# TOP_Sheet.net
KiCad netlist of a schematic drawn in Altium Designer
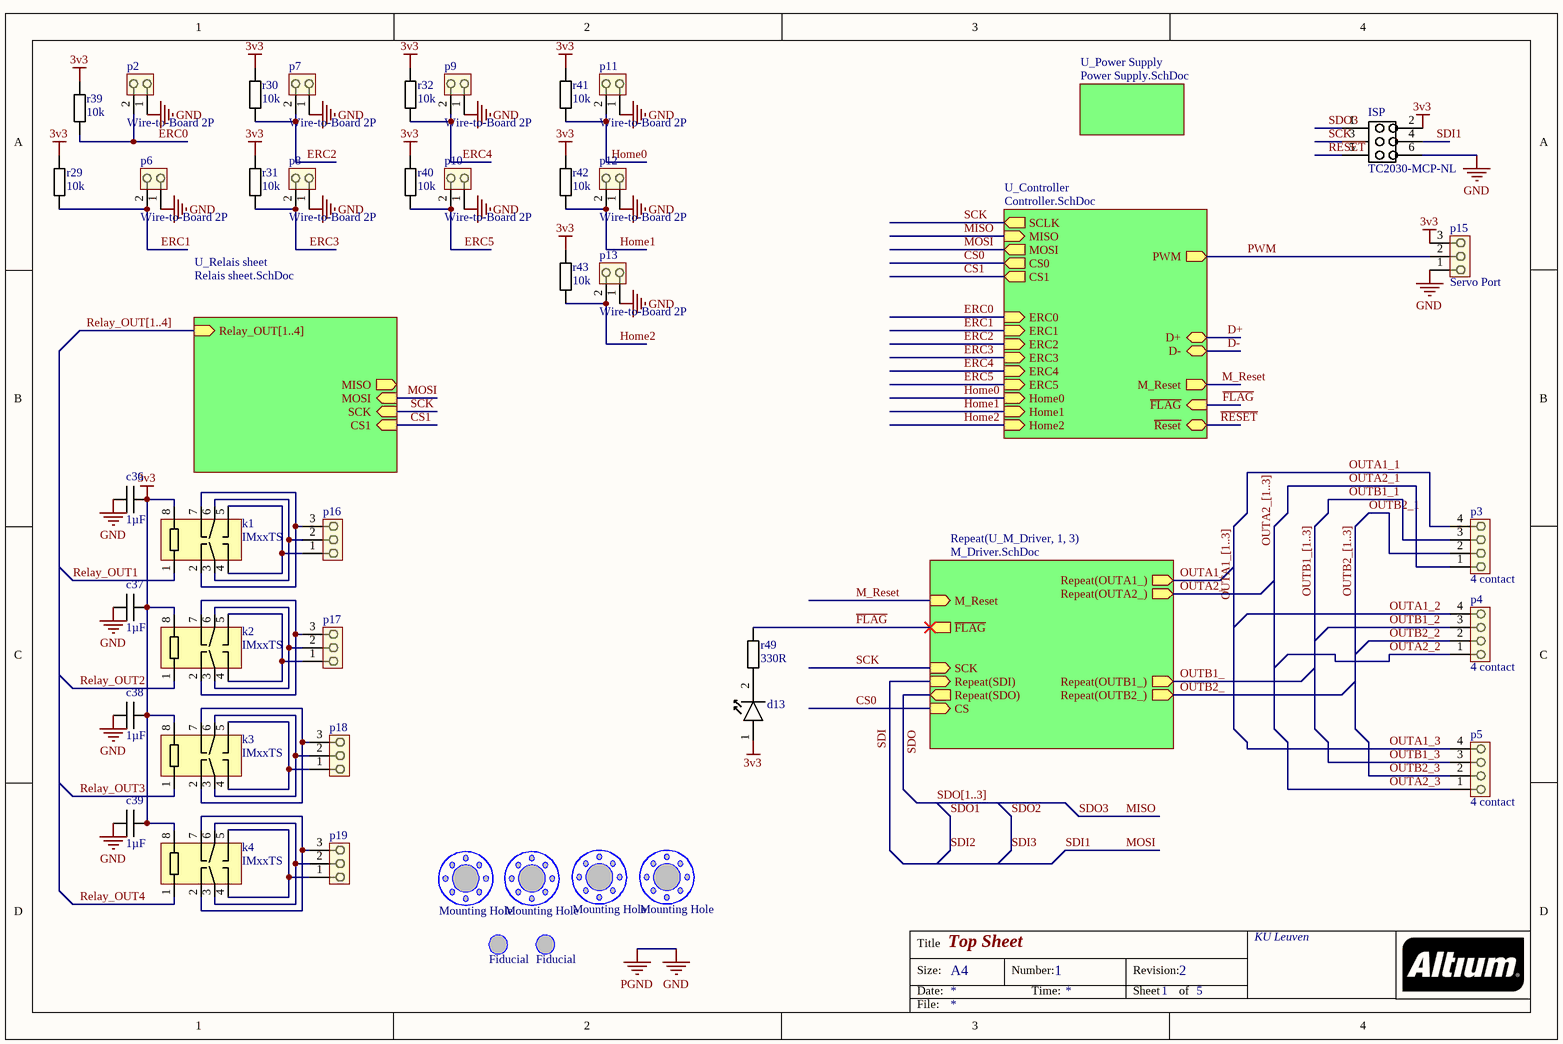
[diagram p0: TOP Sheet.SchDoc]

(export (version "E")
  (design (tool "Eeschema 10.0.6"))
  (components
    (comp (ref "c36")
      (value "1µF")
      (footprint "0805")
      (description "...F")
      (libsource (lib "Generic R-C") (part "0805 Capacitor"))
    )
    (comp (ref "c37")
      (value "1µF")
      (footprint "0805")
      (description "...F")
      (libsource (lib "Generic R-C") (part "0805 Capacitor"))
    )
    (comp (ref "c38")
      (value "1µF")
      (footprint "0805")
      (description "...F")
      (libsource (lib "Generic R-C") (part "0805 Capacitor"))
    )
    (comp (ref "c39")
      (value "1µF")
      (footprint "0805")
      (description "...F")
      (libsource (lib "Generic R-C") (part "0805 Capacitor"))
    )
    (comp (ref "d13")
      (value "Yellow SMD LED")
      (footprint "0603 - LED")
      (description "0603 Package")
      (libsource (lib "Kingbright") (part "Yellow SMD LED"))
    )
    (comp (ref "f3")
      (value "Fiducial")
      (footprint "Fiducial")
      (libsource (lib "Board_Props") (part "Fiducial"))
    )
    (comp (ref "f4")
      (value "Fiducial")
      (footprint "Fiducial")
      (libsource (lib "Board_Props") (part "Fiducial"))
    )
    (comp (ref "H1")
      (value "Mounting Hole")
      (footprint "Mounting Hole")
      (libsource (lib "Board_Props") (part "Mounting Hole"))
    )
    (comp (ref "H2")
      (value "Mounting Hole")
      (footprint "Mounting Hole")
      (libsource (lib "Board_Props") (part "Mounting Hole"))
    )
    (comp (ref "H3")
      (value "Mounting Hole")
      (footprint "Mounting Hole")
      (libsource (lib "Board_Props") (part "Mounting Hole"))
    )
    (comp (ref "H4")
      (value "Mounting Hole")
      (footprint "Mounting Hole")
      (libsource (lib "Board_Props") (part "Mounting Hole"))
    )
    (comp (ref "ISP")
      (value "TC2030-MCP-NL")
      (footprint "2x3-HeaderPin")
      (description "Header Pin")
      (libsource (lib "Multicomp") (part "2x3 Header"))
    )
    (comp (ref "k1")
      (value "IMxxTS")
      (footprint "THT-8")
      (description "Standard THT Package")
      (libsource (lib "TE Connectivity") (part "IMxxTS"))
    )
    (comp (ref "k2")
      (value "IMxxTS")
      (footprint "THT-8")
      (description "Standard THT Package")
      (libsource (lib "TE Connectivity") (part "IMxxTS"))
    )
    (comp (ref "k3")
      (value "IMxxTS")
      (footprint "THT-8")
      (description "Standard THT Package")
      (libsource (lib "TE Connectivity") (part "IMxxTS"))
    )
    (comp (ref "k4")
      (value "IMxxTS")
      (footprint "THT-8")
      (description "Standard THT Package")
      (libsource (lib "TE Connectivity") (part "IMxxTS"))
    )
    (comp (ref "p2")
      (value "Wire-to-Board 2P")
      (footprint "WtB-F-2p_V")
      (libsource (lib "Wurth Electronic") (part "Wire-to-Board 2P"))
    )
    (comp (ref "p3")
      (value "4 contact")
      (footprint "WtB-F-4p")
      (description "Wire-to-Board connector")
      (libsource (lib "Wurth Electronic") (part "Wire-to-Board connector 4 contacts"))
    )
    (comp (ref "p4")
      (value "4 contact")
      (footprint "WtB-F-4p")
      (description "Wire-to-Board connector")
      (libsource (lib "Wurth Electronic") (part "Wire-to-Board connector 4 contacts"))
    )
    (comp (ref "p5")
      (value "4 contact")
      (footprint "WtB-F-4p")
      (description "Wire-to-Board connector")
      (libsource (lib "Wurth Electronic") (part "Wire-to-Board connector 4 contacts"))
    )
    (comp (ref "p6")
      (value "Wire-to-Board 2P")
      (footprint "WtB-F-2p_V")
      (libsource (lib "Wurth Electronic") (part "Wire-to-Board 2P"))
    )
    (comp (ref "p7")
      (value "Wire-to-Board 2P")
      (footprint "WtB-F-2p_V")
      (libsource (lib "Wurth Electronic") (part "Wire-to-Board 2P"))
    )
    (comp (ref "p8")
      (value "Wire-to-Board 2P")
      (footprint "WtB-F-2p_V")
      (libsource (lib "Wurth Electronic") (part "Wire-to-Board 2P"))
    )
    (comp (ref "p9")
      (value "Wire-to-Board 2P")
      (footprint "WtB-F-2p_V")
      (libsource (lib "Wurth Electronic") (part "Wire-to-Board 2P"))
    )
    (comp (ref "p10")
      (value "Wire-to-Board 2P")
      (footprint "WtB-F-2p_V")
      (libsource (lib "Wurth Electronic") (part "Wire-to-Board 2P"))
    )
    (comp (ref "p11")
      (value "Wire-to-Board 2P")
      (footprint "WtB-F-2p_V")
      (libsource (lib "Wurth Electronic") (part "Wire-to-Board 2P"))
    )
    (comp (ref "p12")
      (value "Wire-to-Board 2P")
      (footprint "WtB-F-2p_V")
      (libsource (lib "Wurth Electronic") (part "Wire-to-Board 2P"))
    )
    (comp (ref "p13")
      (value "Wire-to-Board 2P")
      (footprint "WtB-F-2p_V")
      (libsource (lib "Wurth Electronic") (part "Wire-to-Board 2P"))
    )
    (comp (ref "p15")
      (value "Servo Port")
      (footprint "1X3 Headerpin Angled")
      (libsource (lib "Wurth Electronic") (part "Wire-to-Board 3 Pin"))
    )
    (comp (ref "p16")
      (value "Wire-to-Board 3P")
      (footprint "1X3 Headerpin Angled")
      (libsource (lib "Wurth Electronic") (part "Wire-to-Board 3P"))
    )
    (comp (ref "p17")
      (value "Wire-to-Board 3P")
      (footprint "1X3 Headerpin Angled")
      (libsource (lib "Wurth Electronic") (part "Wire-to-Board 3P"))
    )
    (comp (ref "p18")
      (value "Wire-to-Board 3P")
      (footprint "1X3 Headerpin Angled")
      (libsource (lib "Wurth Electronic") (part "Wire-to-Board 3P"))
    )
    (comp (ref "p19")
      (value "Wire-to-Board 3P")
      (footprint "1X3 Headerpin Angled")
      (libsource (lib "Wurth Electronic") (part "Wire-to-Board 3P"))
    )
    (comp (ref "r29")
      (value "10k")
      (footprint "0603")
      (description "...R")
      (libsource (lib "Generic R-C") (part "0603 Resistor"))
    )
    (comp (ref "r30")
      (value "10k")
      (footprint "0603")
      (description "...R")
      (libsource (lib "Generic R-C") (part "0603 Resistor"))
    )
    (comp (ref "r31")
      (value "10k")
      (footprint "0603")
      (description "...R")
      (libsource (lib "Generic R-C") (part "0603 Resistor"))
    )
    (comp (ref "r32")
      (value "10k")
      (footprint "0603")
      (description "...R")
      (libsource (lib "Generic R-C") (part "0603 Resistor"))
    )
    (comp (ref "r39")
      (value "10k")
      (footprint "0603")
      (description "...R")
      (libsource (lib "Generic R-C") (part "0603 Resistor"))
    )
    (comp (ref "r40")
      (value "10k")
      (footprint "0603")
      (description "...R")
      (libsource (lib "Generic R-C") (part "0603 Resistor"))
    )
    (comp (ref "r41")
      (value "10k")
      (footprint "0603")
      (description "...R")
      (libsource (lib "Generic R-C") (part "0603 Resistor"))
    )
    (comp (ref "r42")
      (value "10k")
      (footprint "0603")
      (description "...R")
      (libsource (lib "Generic R-C") (part "0603 Resistor"))
    )
    (comp (ref "r43")
      (value "10k")
      (footprint "0603")
      (description "...R")
      (libsource (lib "Generic R-C") (part "0603 Resistor"))
    )
    (comp (ref "r49")
      (value "330R")
      (footprint "0603")
      (description "...R")
      (libsource (lib "Generic R-C") (part "0603 Resistor"))
    )
  )
  (nets
    (net (code "5") (name "/ERC0") (class "Default")
      (node (ref "p2") (pin "2") (pinfunction "2_2") (pintype "passive"))
      (node (ref "r39") (pin "1") (pintype "passive"))
    )
    (net (code "6") (name "/ERC1") (class "Default")
      (node (ref "p6") (pin "2") (pinfunction "2_2") (pintype "passive"))
      (node (ref "r29") (pin "1") (pintype "passive"))
    )
    (net (code "7") (name "/ERC2") (class "Default")
      (node (ref "p7") (pin "2") (pinfunction "2_2") (pintype "passive"))
      (node (ref "r30") (pin "1") (pintype "passive"))
    )
    (net (code "8") (name "/ERC3") (class "Default")
      (node (ref "p8") (pin "2") (pinfunction "2_2") (pintype "passive"))
      (node (ref "r31") (pin "1") (pintype "passive"))
    )
    (net (code "9") (name "/ERC4") (class "Default")
      (node (ref "p9") (pin "2") (pinfunction "2_2") (pintype "passive"))
      (node (ref "r32") (pin "1") (pintype "passive"))
    )
    (net (code "10") (name "/ERC5") (class "Default")
      (node (ref "p10") (pin "2") (pinfunction "2_2") (pintype "passive"))
      (node (ref "r40") (pin "1") (pintype "passive"))
    )
    (net (code "11") (name "/Home0") (class "Default")
      (node (ref "p11") (pin "2") (pinfunction "2_2") (pintype "passive"))
      (node (ref "r41") (pin "1") (pintype "passive"))
    )
    (net (code "12") (name "/Home1") (class "Default")
      (node (ref "p12") (pin "2") (pinfunction "2_2") (pintype "passive"))
      (node (ref "r42") (pin "1") (pintype "passive"))
    )
    (net (code "13") (name "/Home2") (class "Default")
      (node (ref "p13") (pin "2") (pinfunction "2_2") (pintype "passive"))
      (node (ref "r43") (pin "1") (pintype "passive"))
    )
    (net (code "15") (name "/MOSI") (class "Default")
      (node (ref "ISP") (pin "4") (pinfunction "4_4") (pintype "passive"))
    )
    (net (code "18") (name "/OUTA1_1") (class "Default")
      (node (ref "p3") (pin "4") (pinfunction "4_4") (pintype "passive"))
    )
    (net (code "19") (name "/OUTA1_2") (class "Default")
      (node (ref "p4") (pin "4") (pinfunction "4_4") (pintype "passive"))
    )
    (net (code "20") (name "/OUTA1_3") (class "Default")
      (node (ref "p5") (pin "4") (pinfunction "4_4") (pintype "passive"))
    )
    (net (code "23") (name "/OUTA2_1") (class "Default")
      (node (ref "p3") (pin "1") (pinfunction "1_1") (pintype "passive"))
    )
    (net (code "24") (name "/OUTA2_2") (class "Default")
      (node (ref "p4") (pin "1") (pinfunction "1_1") (pintype "passive"))
    )
    (net (code "25") (name "/OUTA2_3") (class "Default")
      (node (ref "p5") (pin "1") (pinfunction "1_1") (pintype "passive"))
    )
    (net (code "28") (name "/OUTB1_1") (class "Default")
      (node (ref "p3") (pin "3") (pinfunction "3_3") (pintype "passive"))
    )
    (net (code "29") (name "/OUTB1_2") (class "Default")
      (node (ref "p4") (pin "3") (pinfunction "3_3") (pintype "passive"))
    )
    (net (code "30") (name "/OUTB1_3") (class "Default")
      (node (ref "p5") (pin "3") (pinfunction "3_3") (pintype "passive"))
    )
    (net (code "33") (name "/OUTB2_1") (class "Default")
      (node (ref "p3") (pin "2") (pinfunction "2_2") (pintype "passive"))
    )
    (net (code "34") (name "/OUTB2_2") (class "Default")
      (node (ref "p4") (pin "2") (pinfunction "2_2") (pintype "passive"))
    )
    (net (code "35") (name "/OUTB2_3") (class "Default")
      (node (ref "p5") (pin "2") (pinfunction "2_2") (pintype "passive"))
    )
    (net (code "37") (name "/PWM") (class "Default")
      (node (ref "p15") (pin "2") (pinfunction "2_2") (pintype "passive"))
    )
    (net (code "38") (name "/Relay_OUT1") (class "Default")
      (node (ref "k1") (pin "1") (pinfunction "1_1") (pintype "passive"))
    )
    (net (code "39") (name "/Relay_OUT2") (class "Default")
      (node (ref "k2") (pin "1") (pinfunction "1_1") (pintype "passive"))
    )
    (net (code "40") (name "/Relay_OUT3") (class "Default")
      (node (ref "k3") (pin "1") (pinfunction "1_1") (pintype "passive"))
    )
    (net (code "41") (name "/Relay_OUT4") (class "Default")
      (node (ref "k4") (pin "1") (pinfunction "1_1") (pintype "passive"))
    )
    (net (code "43") (name "/SCK") (class "Default")
      (node (ref "ISP") (pin "3") (pinfunction "3_3") (pintype "passive"))
    )
    (net (code "48") (name "/SDO3") (class "Default")
      (node (ref "ISP") (pin "1") (pinfunction "1_1") (pintype "passive"))
    )
    (net (code "50") (name "/~{FLAG}") (class "Default")
      (node (ref "r49") (pin "2") (pintype "passive+no_connect"))
    )
    (net (code "51") (name "/~{RESET}") (class "Default")
      (node (ref "ISP") (pin "5") (pinfunction "5_5") (pintype "passive"))
    )
    (net (code "52") (name "3v3") (class "Default")
      (node (ref "ISP") (pin "2") (pinfunction "2_2") (pintype "passive"))
      (node (ref "c36") (pin "2") (pintype "passive"))
      (node (ref "c37") (pin "2") (pintype "passive"))
      (node (ref "c38") (pin "2") (pintype "passive"))
      (node (ref "c39") (pin "2") (pintype "passive"))
      (node (ref "d13") (pin "1") (pinfunction "Anode_1") (pintype "passive"))
      (node (ref "k1") (pin "8") (pinfunction "8_8") (pintype "passive"))
      (node (ref "k2") (pin "8") (pinfunction "8_8") (pintype "passive"))
      (node (ref "k3") (pin "8") (pinfunction "8_8") (pintype "passive"))
      (node (ref "k4") (pin "8") (pinfunction "8_8") (pintype "passive"))
      (node (ref "p15") (pin "3") (pinfunction "3_3") (pintype "passive"))
      (node (ref "r29") (pin "2") (pintype "passive"))
      (node (ref "r30") (pin "2") (pintype "passive"))
      (node (ref "r31") (pin "2") (pintype "passive"))
      (node (ref "r32") (pin "2") (pintype "passive"))
      (node (ref "r39") (pin "2") (pintype "passive"))
      (node (ref "r40") (pin "2") (pintype "passive"))
      (node (ref "r41") (pin "2") (pintype "passive"))
      (node (ref "r42") (pin "2") (pintype "passive"))
      (node (ref "r43") (pin "2") (pintype "passive"))
    )
    (net (code "53") (name "GND") (class "Default")
      (node (ref "ISP") (pin "6") (pinfunction "6_6") (pintype "passive"))
      (node (ref "c36") (pin "1") (pintype "passive"))
      (node (ref "c37") (pin "1") (pintype "passive"))
      (node (ref "c38") (pin "1") (pintype "passive"))
      (node (ref "c39") (pin "1") (pintype "passive"))
      (node (ref "p10") (pin "1") (pinfunction "1_1") (pintype "passive"))
      (node (ref "p11") (pin "1") (pinfunction "1_1") (pintype "passive"))
      (node (ref "p12") (pin "1") (pinfunction "1_1") (pintype "passive"))
      (node (ref "p13") (pin "1") (pinfunction "1_1") (pintype "passive"))
      (node (ref "p15") (pin "1") (pinfunction "1_1") (pintype "passive"))
      (node (ref "p2") (pin "1") (pinfunction "1_1") (pintype "passive"))
      (node (ref "p6") (pin "1") (pinfunction "1_1") (pintype "passive"))
      (node (ref "p7") (pin "1") (pinfunction "1_1") (pintype "passive"))
      (node (ref "p8") (pin "1") (pinfunction "1_1") (pintype "passive"))
      (node (ref "p9") (pin "1") (pinfunction "1_1") (pintype "passive"))
    )
    (net (code "54") (name "Net-(d13-Kathode)") (class "Default")
      (node (ref "d13") (pin "2") (pinfunction "Kathode_2") (pintype "passive"))
      (node (ref "r49") (pin "1") (pintype "passive"))
    )
    (net (code "55") (name "Net-(k1-Pad2)") (class "Default")
      (node (ref "k1") (pin "2") (pinfunction "2_2") (pintype "passive"))
      (node (ref "k1") (pin "7") (pinfunction "7_7") (pintype "passive"))
      (node (ref "p16") (pin "3") (pinfunction "3_3") (pintype "passive"))
    )
    (net (code "56") (name "Net-(k1-Pad3)") (class "Default")
      (node (ref "k1") (pin "3") (pinfunction "3_3") (pintype "passive"))
      (node (ref "k1") (pin "6") (pinfunction "6_6") (pintype "passive"))
      (node (ref "p16") (pin "2") (pinfunction "2_2") (pintype "passive"))
    )
    (net (code "57") (name "Net-(k1-Pad4)") (class "Default")
      (node (ref "k1") (pin "4") (pinfunction "4_4") (pintype "passive"))
      (node (ref "k1") (pin "5") (pinfunction "5_5") (pintype "passive"))
      (node (ref "p16") (pin "1") (pinfunction "1_1") (pintype "passive"))
    )
    (net (code "58") (name "Net-(k2-Pad2)") (class "Default")
      (node (ref "k2") (pin "2") (pinfunction "2_2") (pintype "passive"))
      (node (ref "k2") (pin "7") (pinfunction "7_7") (pintype "passive"))
      (node (ref "p17") (pin "3") (pinfunction "3_3") (pintype "passive"))
    )
    (net (code "59") (name "Net-(k2-Pad3)") (class "Default")
      (node (ref "k2") (pin "3") (pinfunction "3_3") (pintype "passive"))
      (node (ref "k2") (pin "6") (pinfunction "6_6") (pintype "passive"))
      (node (ref "p17") (pin "2") (pinfunction "2_2") (pintype "passive"))
    )
    (net (code "60") (name "Net-(k2-Pad4)") (class "Default")
      (node (ref "k2") (pin "4") (pinfunction "4_4") (pintype "passive"))
      (node (ref "k2") (pin "5") (pinfunction "5_5") (pintype "passive"))
      (node (ref "p17") (pin "1") (pinfunction "1_1") (pintype "passive"))
    )
    (net (code "61") (name "Net-(k3-Pad2)") (class "Default")
      (node (ref "k3") (pin "2") (pinfunction "2_2") (pintype "passive"))
      (node (ref "k3") (pin "7") (pinfunction "7_7") (pintype "passive"))
      (node (ref "p18") (pin "3") (pinfunction "3_3") (pintype "passive"))
    )
    (net (code "62") (name "Net-(k3-Pad3)") (class "Default")
      (node (ref "k3") (pin "3") (pinfunction "3_3") (pintype "passive"))
      (node (ref "k3") (pin "6") (pinfunction "6_6") (pintype "passive"))
      (node (ref "p18") (pin "2") (pinfunction "2_2") (pintype "passive"))
    )
    (net (code "63") (name "Net-(k3-Pad4)") (class "Default")
      (node (ref "k3") (pin "4") (pinfunction "4_4") (pintype "passive"))
      (node (ref "k3") (pin "5") (pinfunction "5_5") (pintype "passive"))
      (node (ref "p18") (pin "1") (pinfunction "1_1") (pintype "passive"))
    )
    (net (code "64") (name "Net-(k4-Pad2)") (class "Default")
      (node (ref "k4") (pin "2") (pinfunction "2_2") (pintype "passive"))
      (node (ref "k4") (pin "7") (pinfunction "7_7") (pintype "passive"))
      (node (ref "p19") (pin "3") (pinfunction "3_3") (pintype "passive"))
    )
    (net (code "65") (name "Net-(k4-Pad3)") (class "Default")
      (node (ref "k4") (pin "3") (pinfunction "3_3") (pintype "passive"))
      (node (ref "k4") (pin "6") (pinfunction "6_6") (pintype "passive"))
      (node (ref "p19") (pin "2") (pinfunction "2_2") (pintype "passive"))
    )
    (net (code "66") (name "Net-(k4-Pad4)") (class "Default")
      (node (ref "k4") (pin "4") (pinfunction "4_4") (pintype "passive"))
      (node (ref "k4") (pin "5") (pinfunction "5_5") (pintype "passive"))
      (node (ref "p19") (pin "1") (pinfunction "1_1") (pintype "passive"))
    )
  )
)
